# usb-can.net
KiCad netlist of a schematic drawn in EAGLE
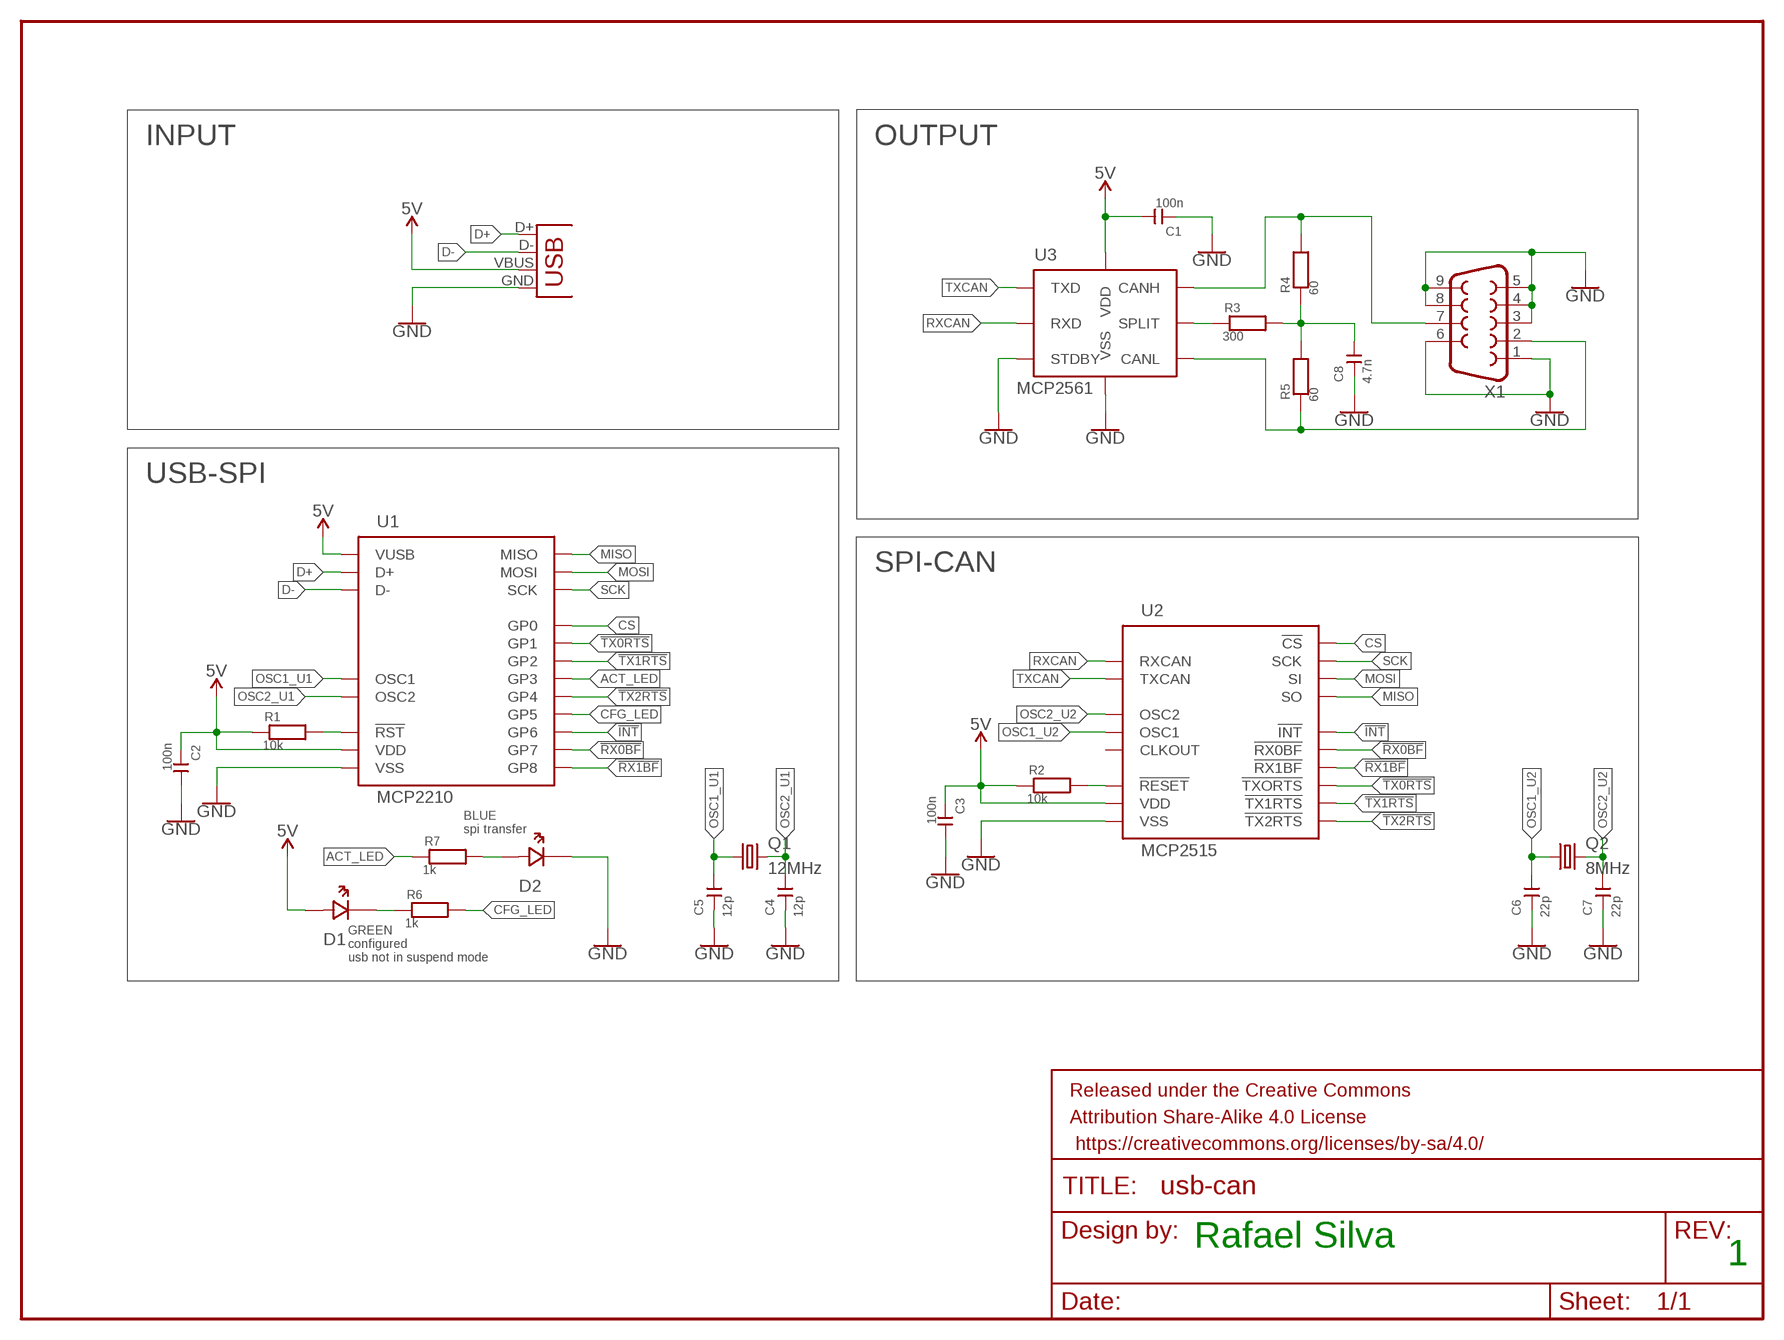
[diagram p0: schematic, sheet 1]

(export (version "E")
  (design (tool "Eeschema 10.0.6"))
  (components
    (comp (ref "C1")
      (value "100n")
      (footprint "eagle-import:0603_WAVE")
      (libsource (lib "eagle-import") (part "CAPSMD"))
    )
    (comp (ref "C2")
      (value "100n")
      (footprint "eagle-import:0603_WAVE")
      (libsource (lib "eagle-import") (part "CAPSMD"))
    )
    (comp (ref "C3")
      (value "100n")
      (footprint "eagle-import:0603_WAVE")
      (libsource (lib "eagle-import") (part "CAPSMD"))
    )
    (comp (ref "C4")
      (value "12p")
      (footprint "eagle-import:0603_WAVE")
      (libsource (lib "eagle-import") (part "CAPSMD"))
    )
    (comp (ref "C5")
      (value "12p")
      (footprint "eagle-import:0603_WAVE")
      (libsource (lib "eagle-import") (part "CAPSMD"))
    )
    (comp (ref "C6")
      (value "22p")
      (footprint "eagle-import:0603_WAVE")
      (libsource (lib "eagle-import") (part "CAPSMD"))
    )
    (comp (ref "C7")
      (value "22p")
      (footprint "eagle-import:0603_WAVE")
      (libsource (lib "eagle-import") (part "CAPSMD"))
    )
    (comp (ref "C8")
      (value "4.7n")
      (footprint "eagle-import:0603_WAVE")
      (libsource (lib "eagle-import") (part "CAPSMD"))
    )
    (comp (ref "D1")
      (value "RED(nok)")
      (footprint "eagle-import:0603_LED")
      (libsource (lib "eagle-import") (part "SML-D12"))
    )
    (comp (ref "D2")
      (value "SML-D12")
      (footprint "eagle-import:0603_LED")
      (libsource (lib "eagle-import") (part "SML-D12"))
    )
    (comp (ref "FRAME1")
      (value "FRAME-LETTERNO_PACKAGE")
      (footprint "eagle-import:DUMMY")
      (fields (field (name "DESIGNER") "Nobody"))
      (libsource (lib "eagle-import") (part "FRAME-LETTERNO_PACKAGE"))
    )
    (comp (ref "Q1")
      (value "12MHz")
      (footprint "eagle-import:SM49")
      (libsource (lib "eagle-import") (part "CRYSTALSM49"))
    )
    (comp (ref "Q2")
      (value "8MHz")
      (footprint "eagle-import:SM49")
      (libsource (lib "eagle-import") (part "CRYSTALSM49"))
    )
    (comp (ref "R1")
      (value "10k")
      (footprint "eagle-import:0603_WAVE")
      (libsource (lib "eagle-import") (part "RES0603"))
    )
    (comp (ref "R2")
      (value "10k")
      (footprint "eagle-import:0603_WAVE")
      (libsource (lib "eagle-import") (part "RES0603"))
    )
    (comp (ref "R3")
      (value "300")
      (footprint "eagle-import:0603_WAVE")
      (libsource (lib "eagle-import") (part "RES0603"))
    )
    (comp (ref "R4")
      (value "60")
      (footprint "eagle-import:0603_WAVE")
      (libsource (lib "eagle-import") (part "RES0603"))
    )
    (comp (ref "R5")
      (value "60")
      (footprint "eagle-import:0603_WAVE")
      (libsource (lib "eagle-import") (part "RES0603"))
    )
    (comp (ref "R6")
      (value "1k")
      (footprint "eagle-import:0603_WAVE")
      (libsource (lib "eagle-import") (part "RES0603"))
    )
    (comp (ref "R7")
      (value "1k")
      (footprint "eagle-import:0603_WAVE")
      (libsource (lib "eagle-import") (part "RES0603"))
    )
    (comp (ref "U1")
      (value "MCP2210")
      (footprint "eagle-import:SOIC-20_300MIL")
      (libsource (lib "eagle-import") (part "MCP2210"))
    )
    (comp (ref "U2")
      (value "MCP2515")
      (footprint "eagle-import:SOIC-18_300MIL")
      (libsource (lib "eagle-import") (part "MCP2515"))
    )
    (comp (ref "U3")
      (value "MCP2561")
      (footprint "eagle-import:SOIC_8")
      (libsource (lib "eagle-import") (part "MCP2561"))
    )
    (comp (ref "X1")
      (value "DB9MALE")
      (footprint "eagle-import:DB9_MALE")
      (libsource (lib "eagle-import") (part "DB9MALE"))
    )
    (comp (ref "X2")
      (value "USBPTH")
      (footprint "eagle-import:USB-B-PTH")
      (libsource (lib "eagle-import") (part "USBPTH"))
    )
  )
  (nets
    (net (code "1") (name "/~{INT}") (class "Default")
      (node (ref "U1") (pin "P$14") (pinfunction "GP6_P$14") (pintype "bidirectional"))
      (node (ref "U2") (pin "P$12") (pinfunction "~{INT}_P$12") (pintype "bidirectional"))
    )
    (net (code "2") (name "/~{RX0BF}") (class "Default")
      (node (ref "U1") (pin "P$15") (pinfunction "GP7_P$15") (pintype "bidirectional"))
      (node (ref "U2") (pin "P$11") (pinfunction "~{RX0BF}_P$11") (pintype "bidirectional"))
    )
    (net (code "3") (name "/~{RX1BF}") (class "Default")
      (node (ref "U1") (pin "P$16") (pinfunction "GP8_P$16") (pintype "bidirectional"))
      (node (ref "U2") (pin "P$10") (pinfunction "~{RX1BF}_P$10") (pintype "bidirectional"))
    )
    (net (code "4") (name "/~{TX0RTS}") (class "Default")
      (node (ref "U1") (pin "P$6") (pinfunction "GP1_P$6") (pintype "bidirectional"))
      (node (ref "U2") (pin "P$4") (pinfunction "~{TXORTS}_P$4") (pintype "bidirectional"))
    )
    (net (code "5") (name "/~{TX1RTS}") (class "Default")
      (node (ref "U1") (pin "P$7") (pinfunction "GP2_P$7") (pintype "bidirectional"))
      (node (ref "U2") (pin "P$5") (pinfunction "~{TX1RTS}_P$5") (pintype "bidirectional"))
    )
    (net (code "6") (name "/~{TX2RTS}") (class "Default")
      (node (ref "U1") (pin "P$10") (pinfunction "GP4_P$10") (pintype "bidirectional"))
      (node (ref "U2") (pin "P$6") (pinfunction "~{TX2RTS}_P$6") (pintype "bidirectional"))
    )
    (net (code "7") (name "5V") (class "Default")
      (node (ref "C1") (pin "P$2") (pinfunction "P$2_P$2") (pintype "bidirectional"))
      (node (ref "C2") (pin "P$1") (pinfunction "P$1_P$1") (pintype "bidirectional"))
      (node (ref "C3") (pin "P$1") (pinfunction "P$1_P$1") (pintype "bidirectional"))
      (node (ref "D1") (pin "P$2") (pinfunction "AN_P$2") (pintype "bidirectional"))
      (node (ref "R1") (pin "P$1") (pinfunction "P$1_P$1") (pintype "bidirectional"))
      (node (ref "R2") (pin "P$1") (pinfunction "P$1_P$1") (pintype "bidirectional"))
      (node (ref "U1") (pin "P$1") (pinfunction "VDD_P$1") (pintype "bidirectional"))
      (node (ref "U1") (pin "P$17") (pinfunction "VUSB_P$17") (pintype "bidirectional"))
      (node (ref "U2") (pin "P$18") (pinfunction "VDD_P$18") (pintype "bidirectional"))
      (node (ref "U3") (pin "P$3") (pinfunction "VDD_P$3") (pintype "bidirectional"))
      (node (ref "X2") (pin "VBUS") (pinfunction "VBUS_VBUS") (pintype "bidirectional"))
    )
    (net (code "8") (name "ACT_LED") (class "Default")
      (node (ref "R7") (pin "P$1") (pinfunction "P$1_P$1") (pintype "bidirectional"))
      (node (ref "U1") (pin "P$8") (pinfunction "GP3_P$8") (pintype "bidirectional"))
    )
    (net (code "9") (name "CFG_LED") (class "Default")
      (node (ref "R6") (pin "P$2") (pinfunction "P$2_P$2") (pintype "bidirectional"))
      (node (ref "U1") (pin "P$12") (pinfunction "GP5_P$12") (pintype "bidirectional"))
    )
    (net (code "10") (name "CS") (class "Default")
      (node (ref "U1") (pin "P$5") (pinfunction "GP0_P$5") (pintype "bidirectional"))
      (node (ref "U2") (pin "P$16") (pinfunction "~{CS}_P$16") (pintype "bidirectional"))
    )
    (net (code "11") (name "D+") (class "Default")
      (node (ref "U1") (pin "P$19") (pinfunction "D+_P$19") (pintype "bidirectional"))
      (node (ref "X2") (pin "D+") (pinfunction "D+_D+") (pintype "bidirectional"))
    )
    (net (code "12") (name "D-") (class "Default")
      (node (ref "U1") (pin "P$18") (pinfunction "D-_P$18") (pintype "bidirectional"))
      (node (ref "X2") (pin "D-") (pinfunction "D-_D-") (pintype "bidirectional"))
    )
    (net (code "13") (name "GND") (class "Default")
      (node (ref "C1") (pin "P$1") (pinfunction "P$1_P$1") (pintype "bidirectional"))
      (node (ref "C2") (pin "P$2") (pinfunction "P$2_P$2") (pintype "bidirectional"))
      (node (ref "C3") (pin "P$2") (pinfunction "P$2_P$2") (pintype "bidirectional"))
      (node (ref "C4") (pin "P$1") (pinfunction "P$1_P$1") (pintype "bidirectional"))
      (node (ref "C5") (pin "P$1") (pinfunction "P$1_P$1") (pintype "bidirectional"))
      (node (ref "C6") (pin "P$1") (pinfunction "P$1_P$1") (pintype "bidirectional"))
      (node (ref "C7") (pin "P$1") (pinfunction "P$1_P$1") (pintype "bidirectional"))
      (node (ref "C8") (pin "P$1") (pinfunction "P$1_P$1") (pintype "bidirectional"))
      (node (ref "D2") (pin "P$1") (pinfunction "CA_P$1") (pintype "bidirectional"))
      (node (ref "U1") (pin "P$20") (pinfunction "VSS_P$20") (pintype "bidirectional"))
      (node (ref "U2") (pin "P$9") (pinfunction "VSS_P$9") (pintype "bidirectional"))
      (node (ref "U3") (pin "P$2") (pinfunction "VSS_P$2") (pintype "bidirectional"))
      (node (ref "U3") (pin "P$8") (pinfunction "STDBY_P$8") (pintype "bidirectional"))
      (node (ref "X1") (pin "1") (pinfunction "1_1") (pintype "passive"))
      (node (ref "X1") (pin "3") (pinfunction "3_3") (pintype "passive"))
      (node (ref "X1") (pin "4") (pinfunction "4_4") (pintype "passive"))
      (node (ref "X1") (pin "5") (pinfunction "5_5") (pintype "passive"))
      (node (ref "X1") (pin "6") (pinfunction "6_6") (pintype "passive"))
      (node (ref "X1") (pin "8") (pinfunction "8_8") (pintype "passive"))
      (node (ref "X1") (pin "9") (pinfunction "9_9") (pintype "passive"))
      (node (ref "X2") (pin "GND") (pinfunction "GND_GND") (pintype "bidirectional"))
    )
    (net (code "14") (name "MISO") (class "Default")
      (node (ref "U1") (pin "P$13") (pinfunction "MISO_P$13") (pintype "bidirectional"))
      (node (ref "U2") (pin "P$15") (pinfunction "SO_P$15") (pintype "bidirectional"))
    )
    (net (code "15") (name "MOSI") (class "Default")
      (node (ref "U1") (pin "P$9") (pinfunction "MOSI_P$9") (pintype "bidirectional"))
      (node (ref "U2") (pin "P$14") (pinfunction "SI_P$14") (pintype "bidirectional"))
    )
    (net (code "16") (name "Net-(C8-PadP$2)") (class "Default")
      (node (ref "C8") (pin "P$2") (pinfunction "P$2_P$2") (pintype "bidirectional"))
      (node (ref "R3") (pin "P$2") (pinfunction "P$2_P$2") (pintype "bidirectional"))
      (node (ref "R4") (pin "P$1") (pinfunction "P$1_P$1") (pintype "bidirectional"))
      (node (ref "R5") (pin "P$2") (pinfunction "P$2_P$2") (pintype "bidirectional"))
    )
    (net (code "17") (name "Net-(D1-CA)") (class "Default")
      (node (ref "D1") (pin "P$1") (pinfunction "CA_P$1") (pintype "bidirectional"))
      (node (ref "R6") (pin "P$1") (pinfunction "P$1_P$1") (pintype "bidirectional"))
    )
    (net (code "18") (name "Net-(D2-AN)") (class "Default")
      (node (ref "D2") (pin "P$2") (pinfunction "AN_P$2") (pintype "bidirectional"))
      (node (ref "R7") (pin "P$2") (pinfunction "P$2_P$2") (pintype "bidirectional"))
    )
    (net (code "19") (name "Net-(U1-~{RST})") (class "Default")
      (node (ref "R1") (pin "P$2") (pinfunction "P$2_P$2") (pintype "bidirectional"))
      (node (ref "U1") (pin "P$4") (pinfunction "~{RST}_P$4") (pintype "bidirectional"))
    )
    (net (code "20") (name "Net-(U2-~{RESET})") (class "Default")
      (node (ref "R2") (pin "P$2") (pinfunction "P$2_P$2") (pintype "bidirectional"))
      (node (ref "U2") (pin "P$17") (pinfunction "~{RESET}_P$17") (pintype "bidirectional"))
    )
    (net (code "21") (name "Net-(U3-CANH)") (class "Default")
      (node (ref "R4") (pin "P$2") (pinfunction "P$2_P$2") (pintype "bidirectional"))
      (node (ref "U3") (pin "P$7") (pinfunction "CANH_P$7") (pintype "bidirectional"))
      (node (ref "X1") (pin "7") (pinfunction "7_7") (pintype "passive"))
    )
    (net (code "22") (name "Net-(U3-CANL)") (class "Default")
      (node (ref "R5") (pin "P$1") (pinfunction "P$1_P$1") (pintype "bidirectional"))
      (node (ref "U3") (pin "P$6") (pinfunction "CANL_P$6") (pintype "bidirectional"))
      (node (ref "X1") (pin "2") (pinfunction "2_2") (pintype "passive"))
    )
    (net (code "23") (name "Net-(U3-SPLIT)") (class "Default")
      (node (ref "R3") (pin "P$1") (pinfunction "P$1_P$1") (pintype "bidirectional"))
      (node (ref "U3") (pin "P$5") (pinfunction "SPLIT_P$5") (pintype "power_in"))
    )
    (net (code "24") (name "OSC1_U1") (class "Default")
      (node (ref "C5") (pin "P$2") (pinfunction "P$2_P$2") (pintype "bidirectional"))
      (node (ref "Q1") (pin "1") (pinfunction "1_1") (pintype "passive"))
      (node (ref "U1") (pin "P$2") (pinfunction "OSC1_P$2") (pintype "bidirectional"))
    )
    (net (code "25") (name "OSC1_U2") (class "Default")
      (node (ref "C6") (pin "P$2") (pinfunction "P$2_P$2") (pintype "bidirectional"))
      (node (ref "Q2") (pin "1") (pinfunction "1_1") (pintype "passive"))
      (node (ref "U2") (pin "P$8") (pinfunction "OSC1_P$8") (pintype "bidirectional"))
    )
    (net (code "26") (name "OSC2_U1") (class "Default")
      (node (ref "C4") (pin "P$2") (pinfunction "P$2_P$2") (pintype "bidirectional"))
      (node (ref "Q1") (pin "2") (pinfunction "2_2") (pintype "passive"))
      (node (ref "U1") (pin "P$3") (pinfunction "OSC2_P$3") (pintype "bidirectional"))
    )
    (net (code "27") (name "OSC2_U2") (class "Default")
      (node (ref "C7") (pin "P$2") (pinfunction "P$2_P$2") (pintype "bidirectional"))
      (node (ref "Q2") (pin "2") (pinfunction "2_2") (pintype "passive"))
      (node (ref "U2") (pin "P$7") (pinfunction "OSC2_P$7") (pintype "bidirectional"))
    )
    (net (code "28") (name "RXCAN") (class "Default")
      (node (ref "U2") (pin "P$2") (pinfunction "RXCAN_P$2") (pintype "bidirectional"))
      (node (ref "U3") (pin "P$4") (pinfunction "RXD_P$4") (pintype "bidirectional"))
    )
    (net (code "29") (name "SCK") (class "Default")
      (node (ref "U1") (pin "P$11") (pinfunction "SCK_P$11") (pintype "bidirectional"))
      (node (ref "U2") (pin "P$13") (pinfunction "SCK_P$13") (pintype "bidirectional"))
    )
    (net (code "30") (name "TXCAN") (class "Default")
      (node (ref "U2") (pin "P$1") (pinfunction "TXCAN_P$1") (pintype "bidirectional"))
      (node (ref "U3") (pin "P$1") (pinfunction "TXD_P$1") (pintype "bidirectional"))
    )
    (net (code "31") (name "unconnected-(U2-CLKOUT-PadP$3)") (class "Default")
      (node (ref "U2") (pin "P$3") (pinfunction "CLKOUT_P$3") (pintype "bidirectional"))
    )
  )
)
